# v0_6_0.net
KiCad netlist of a schematic drawn in EAGLE
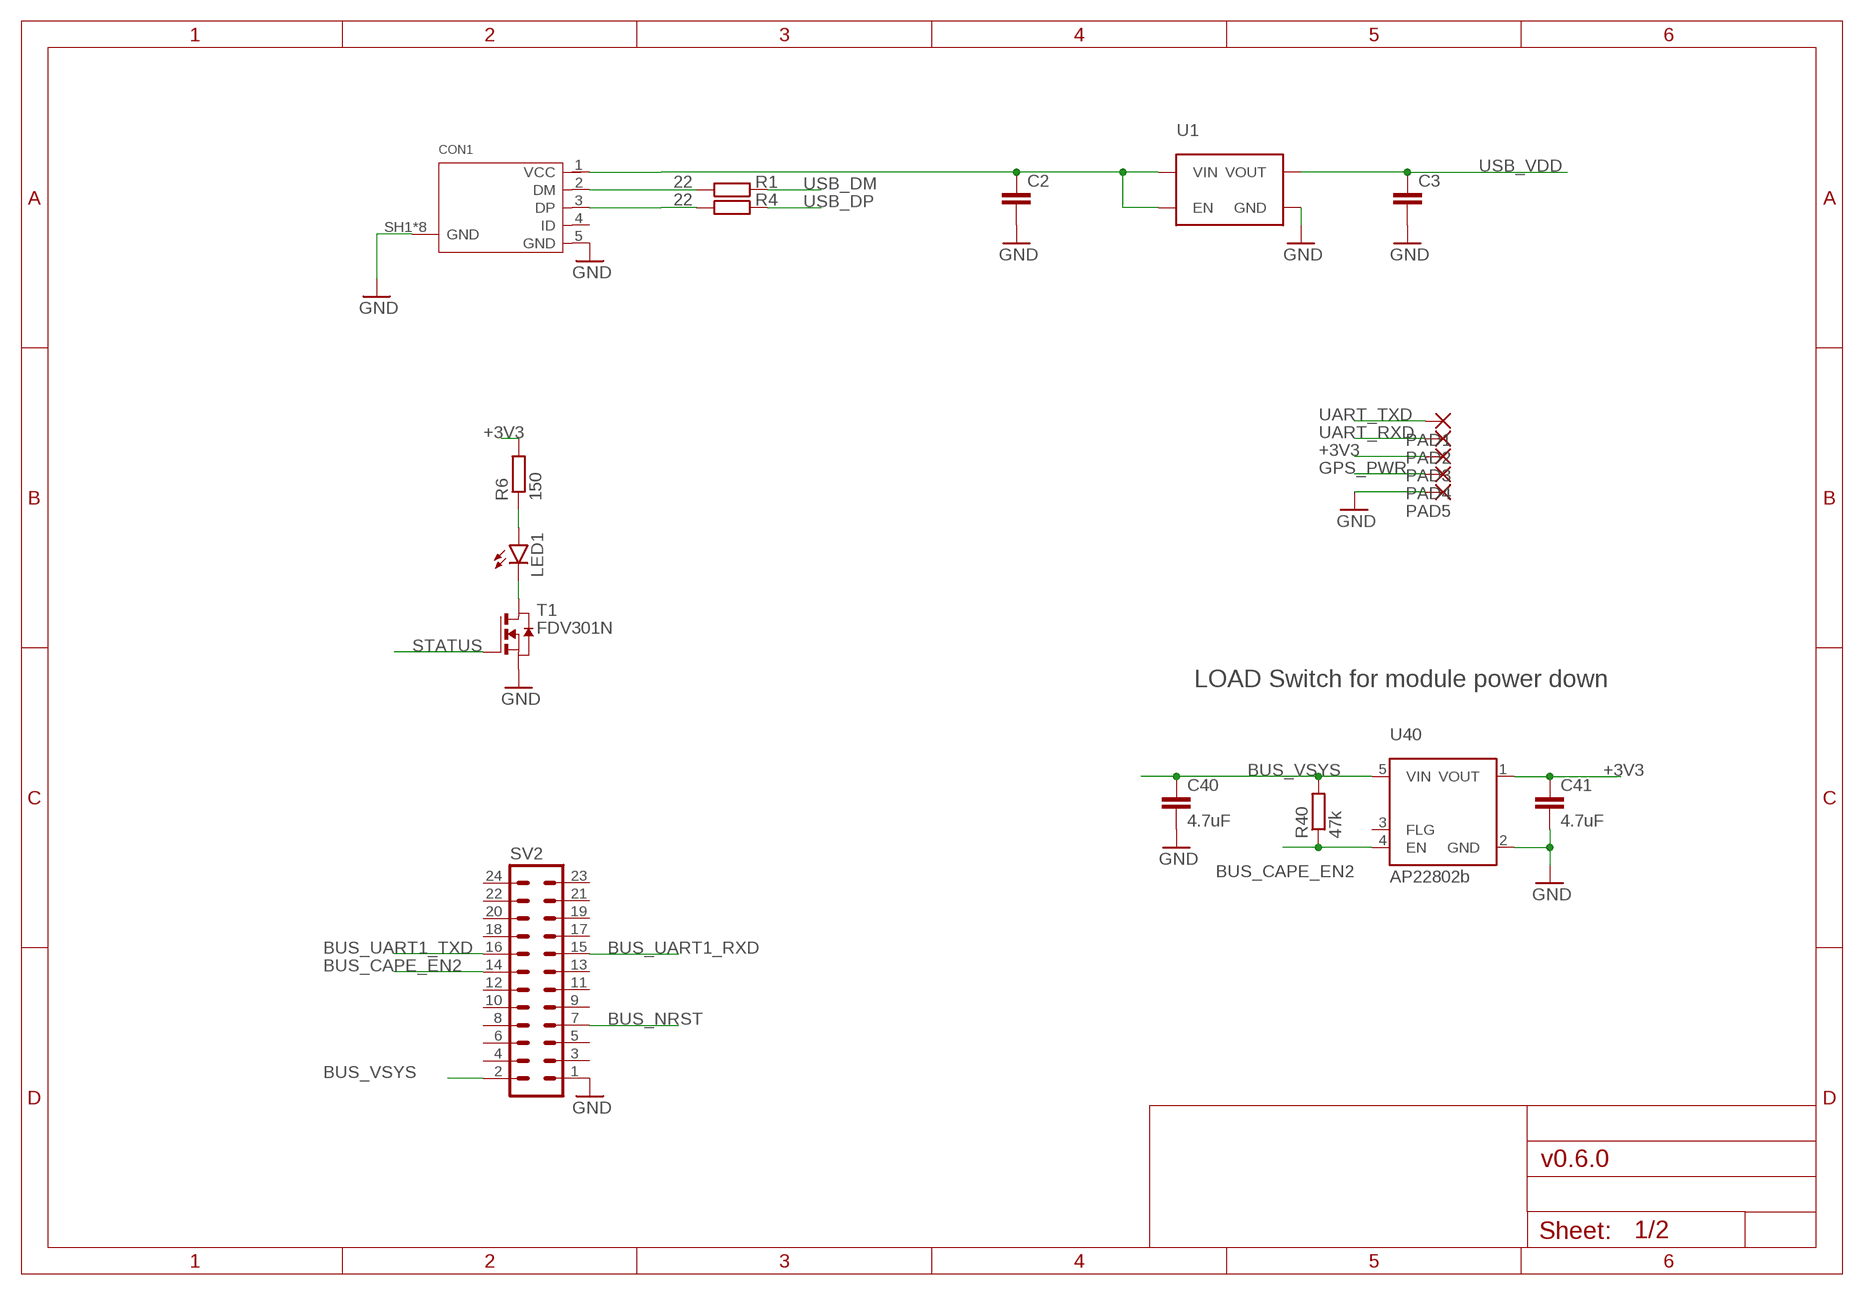
[diagram p0: schematic, sheet 1]
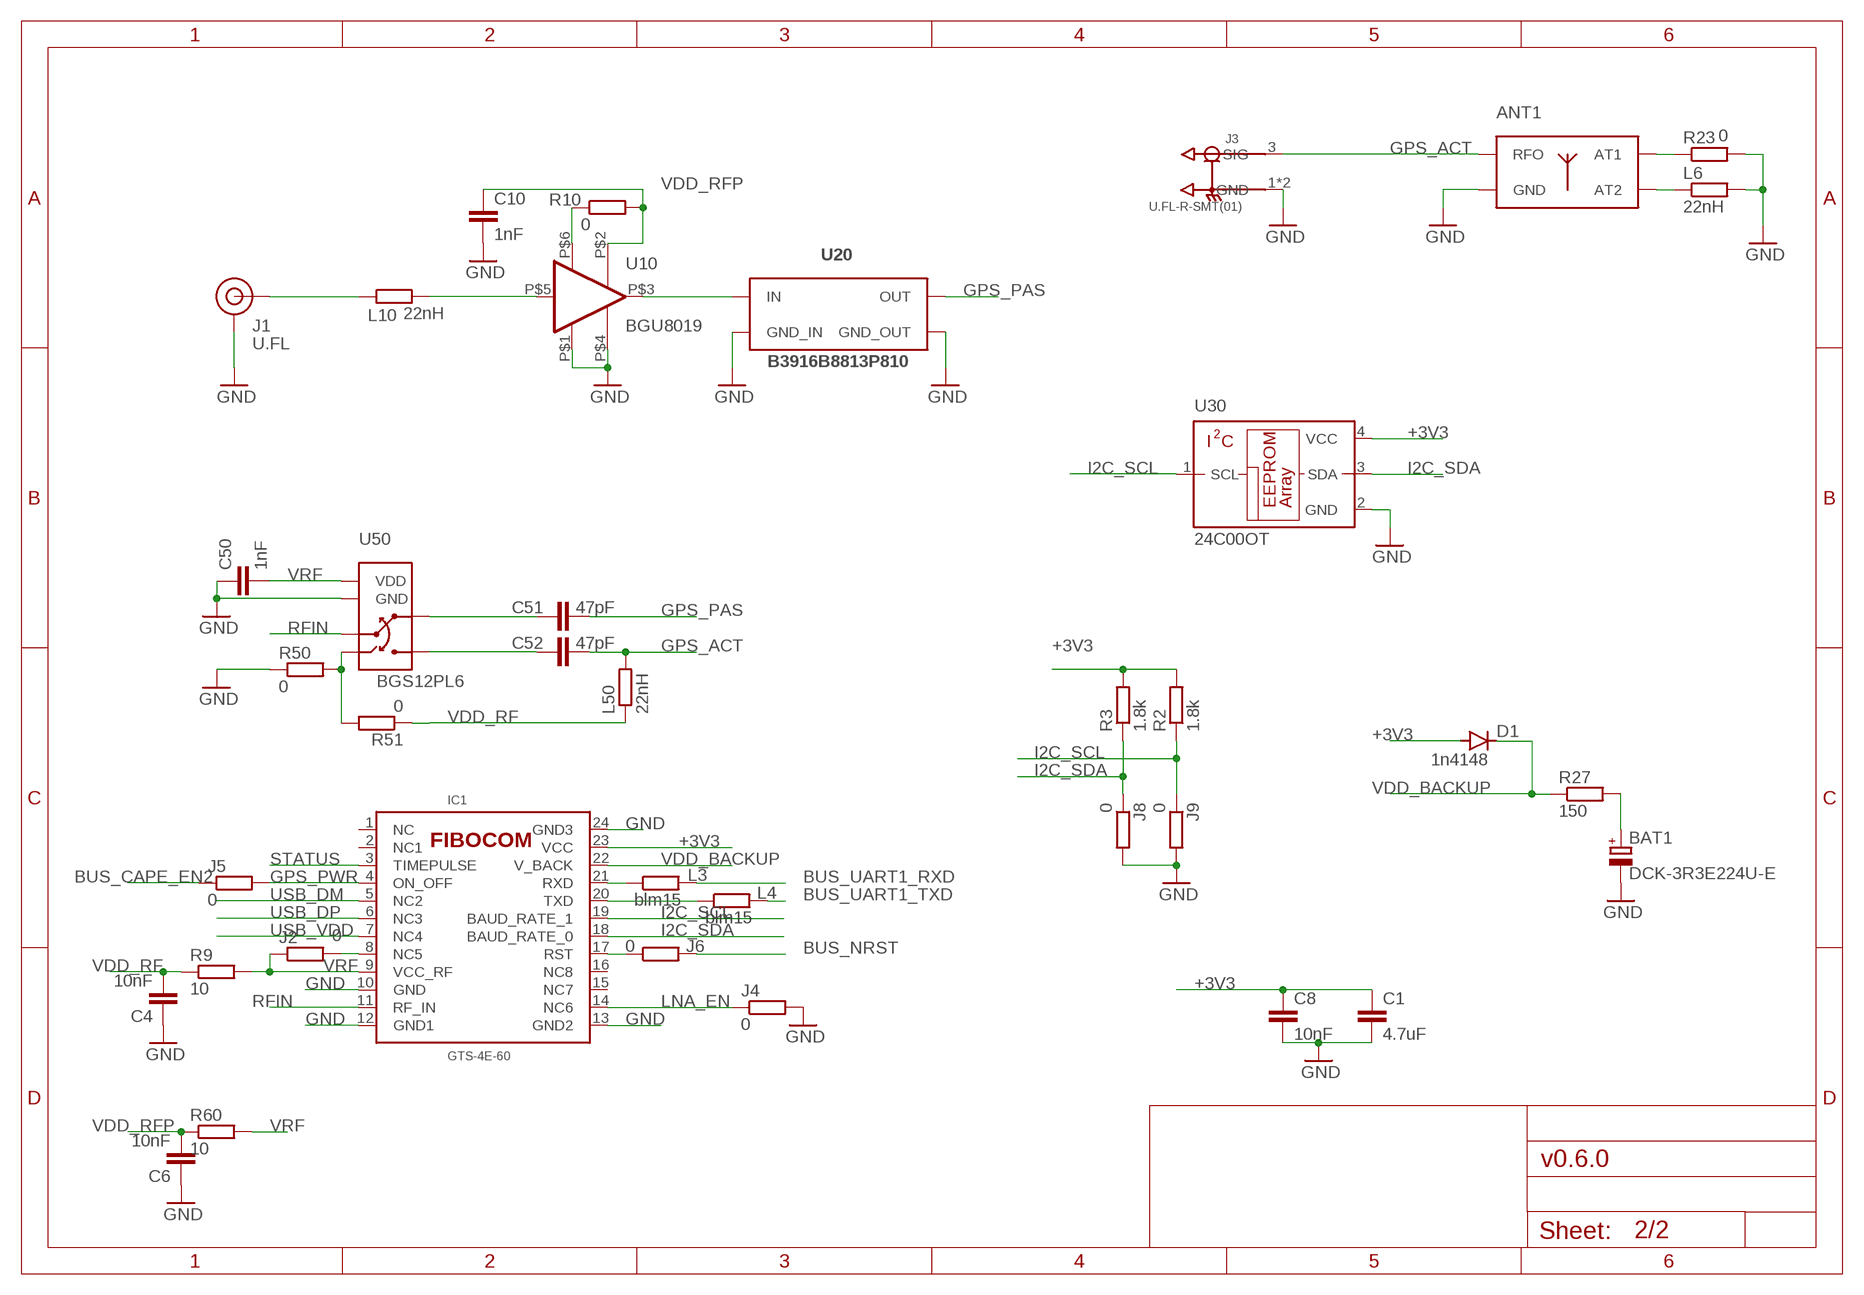
[diagram p1: schematic, sheet 2]

(export (version "E")
  (design (tool "Eeschema 10.0.6"))
  (components
    (comp (ref "ANT1")
      (value "M20047")
      (footprint "eagle-import:PCBCOMPONENT_1")
      (libsource (lib "eagle-import") (part "M20047"))
    )
    (comp (ref "BAT1")
      (value "DCK-3R3E224U-E")
      (footprint "eagle-import:621")
      (libsource (lib "eagle-import") (part "DCK-3R3E224U-E"))
    )
    (comp (ref "C1")
      (value "4.7uF")
      (footprint "eagle-import:C0603")
      (libsource (lib "eagle-import") (part "C-EUC0603"))
    )
    (comp (ref "C4")
      (value "10nF")
      (footprint "eagle-import:C0402")
      (libsource (lib "eagle-import") (part "C-EUC0402"))
    )
    (comp (ref "C6")
      (value "10nF")
      (footprint "eagle-import:C0402")
      (libsource (lib "eagle-import") (part "C-EUC0402"))
    )
    (comp (ref "C8")
      (value "10nF")
      (footprint "eagle-import:C0402")
      (libsource (lib "eagle-import") (part "C-EUC0402"))
    )
    (comp (ref "C10")
      (value "1nF")
      (footprint "eagle-import:C0402")
      (libsource (lib "eagle-import") (part "C-EUC0402"))
    )
    (comp (ref "C50")
      (value "1nF")
      (footprint "eagle-import:C0402")
      (libsource (lib "eagle-import") (part "C-EUC0402"))
    )
    (comp (ref "C51")
      (value "47pF")
      (footprint "eagle-import:C0402")
      (libsource (lib "eagle-import") (part "C-EUC0402"))
    )
    (comp (ref "C52")
      (value "47pF")
      (footprint "eagle-import:C0402")
      (libsource (lib "eagle-import") (part "C-EUC0402"))
    )
    (comp (ref "D1")
      (value "1n4148")
      (footprint "eagle-import:SOD323-R")
      (libsource (lib "eagle-import") (part "DIODE-SOD323-R"))
    )
    (comp (ref "IC1")
      (value "GTS-4E-60")
      (footprint "eagle-import:_GTS_4E_60")
      (libsource (lib "eagle-import") (part "GTS-4E-60"))
    )
    (comp (ref "J1")
      (value "U.FL")
      (footprint "eagle-import:U.FL")
      (libsource (lib "eagle-import") (part "U.FL2PIN"))
    )
    (comp (ref "J2")
      (value "0")
      (footprint "eagle-import:R0402")
      (libsource (lib "eagle-import") (part "R-EU_R0402"))
    )
    (comp (ref "J3")
      (value "U.FL-R-SMT(01)")
      (footprint "eagle-import:HRS_U.FL-R-SMT(01)")
      (fields (field (name "MF") "Hirose") (field (name "MP") "U.FL-R-SMT_01_"))
      (libsource (lib "eagle-import") (part "U.FL-R-SMT(01)"))
    )
    (comp (ref "J4")
      (value "0")
      (footprint "eagle-import:R0402")
      (libsource (lib "eagle-import") (part "R-EU_R0402"))
    )
    (comp (ref "J5")
      (value "0")
      (footprint "eagle-import:R0402")
      (libsource (lib "eagle-import") (part "R-EU_R0402"))
    )
    (comp (ref "J6")
      (value "0")
      (footprint "eagle-import:R0402")
      (libsource (lib "eagle-import") (part "R-EU_R0402"))
    )
    (comp (ref "J8")
      (value "0")
      (footprint "eagle-import:R0402")
      (libsource (lib "eagle-import") (part "R-EU_R0402"))
    )
    (comp (ref "J9")
      (value "0")
      (footprint "eagle-import:R0402")
      (libsource (lib "eagle-import") (part "R-EU_R0402"))
    )
    (comp (ref "L3")
      (value "blm15")
      (footprint "eagle-import:R0402")
      (libsource (lib "eagle-import") (part "R-EU_R0402"))
    )
    (comp (ref "L4")
      (value "blm15")
      (footprint "eagle-import:R0402")
      (libsource (lib "eagle-import") (part "R-EU_R0402"))
    )
    (comp (ref "L6")
      (value "22nH")
      (footprint "eagle-import:R0402")
      (libsource (lib "eagle-import") (part "R-EU_R0402"))
    )
    (comp (ref "L10")
      (value "22nH")
      (footprint "eagle-import:R0402")
      (libsource (lib "eagle-import") (part "R-EU_R0402"))
    )
    (comp (ref "L50")
      (value "22nH")
      (footprint "eagle-import:R0402")
      (libsource (lib "eagle-import") (part "R-EU_R0402"))
    )
    (comp (ref "R2")
      (value "1.8k")
      (footprint "eagle-import:R0402")
      (libsource (lib "eagle-import") (part "R-EU_R0402"))
    )
    (comp (ref "R3")
      (value "1.8k")
      (footprint "eagle-import:R0402")
      (libsource (lib "eagle-import") (part "R-EU_R0402"))
    )
    (comp (ref "R9")
      (value "10")
      (footprint "eagle-import:R0402")
      (libsource (lib "eagle-import") (part "R-EU_R0402"))
    )
    (comp (ref "R10")
      (value "0")
      (footprint "eagle-import:R0402")
      (libsource (lib "eagle-import") (part "R-EU_R0402"))
    )
    (comp (ref "R23")
      (value "0")
      (footprint "eagle-import:R0402")
      (libsource (lib "eagle-import") (part "R-EU_R0402"))
    )
    (comp (ref "R27")
      (value "150")
      (footprint "eagle-import:R0402")
      (libsource (lib "eagle-import") (part "R-EU_R0402"))
    )
    (comp (ref "R50")
      (value "0")
      (footprint "eagle-import:R0402")
      (libsource (lib "eagle-import") (part "R-EU_R0402"))
    )
    (comp (ref "R51")
      (value "0")
      (footprint "eagle-import:R0402")
      (libsource (lib "eagle-import") (part "R-EU_R0402"))
    )
    (comp (ref "R60")
      (value "10")
      (footprint "eagle-import:R0402")
      (libsource (lib "eagle-import") (part "R-EU_R0402"))
    )
    (comp (ref "U10")
      (value "BGU8019")
      (footprint "eagle-import:XSON6")
      (libsource (lib "eagle-import") (part "BGU8019"))
    )
    (comp (ref "U20")
      (value "B3916B8813P810")
      (footprint "eagle-import:XSON5")
      (libsource (lib "eagle-import") (part "B3916B8813P810"))
    )
    (comp (ref "U30")
      (value "24C00OT")
      (footprint "eagle-import:SOT23-5L")
      (fields (field (name "MF") "MICROCHIP") (field (name "MPN") "24C00T-I/OT"))
      (libsource (lib "eagle-import") (part "2400OTC"))
    )
    (comp (ref "U50")
      (value "BGS12PL6")
      (footprint "eagle-import:TSLP-6-4")
      (libsource (lib "eagle-import") (part "BGS12PL6"))
    )
    (comp (ref "C2")
      (value "C-EUC0603")
      (footprint "eagle-import:C0603")
      (libsource (lib "eagle-import") (part "C-EUC0603"))
    )
    (comp (ref "C3")
      (value "C-EUC0603")
      (footprint "eagle-import:C0603")
      (libsource (lib "eagle-import") (part "C-EUC0603"))
    )
    (comp (ref "C40")
      (value "4.7uF")
      (footprint "eagle-import:C0603")
      (libsource (lib "eagle-import") (part "C-EUC0603"))
    )
    (comp (ref "C41")
      (value "4.7uF")
      (footprint "eagle-import:C0603")
      (libsource (lib "eagle-import") (part "C-EUC0603"))
    )
    (comp (ref "CON1")
      (value "10118194-0001LF")
      (footprint "eagle-import:10118194")
      (libsource (lib "eagle-import") (part "10118194-0001LF"))
    )
    (comp (ref "LED1")
      (value "LEDCHIP-LED0603")
      (footprint "eagle-import:CHIP-LED0603")
      (libsource (lib "eagle-import") (part "LEDCHIP-LED0603"))
    )
    (comp (ref "PAD1")
      (value "1,6/0,9")
      (footprint "eagle-import:1,6_0,9")
      (libsource (lib "eagle-import") (part "1,6/0,9"))
    )
    (comp (ref "PAD2")
      (value "1,6/0,9")
      (footprint "eagle-import:1,6_0,9")
      (libsource (lib "eagle-import") (part "1,6/0,9"))
    )
    (comp (ref "PAD3")
      (value "1,6/0,9")
      (footprint "eagle-import:1,6_0,9")
      (libsource (lib "eagle-import") (part "1,6/0,9"))
    )
    (comp (ref "PAD4")
      (value "1,6/0,9")
      (footprint "eagle-import:1,6_0,9")
      (libsource (lib "eagle-import") (part "1,6/0,9"))
    )
    (comp (ref "PAD5")
      (value "1,6/0,9")
      (footprint "eagle-import:1,6_0,9")
      (libsource (lib "eagle-import") (part "1,6/0,9"))
    )
    (comp (ref "R1")
      (value "22")
      (footprint "eagle-import:R0402")
      (libsource (lib "eagle-import") (part "R-EU_R0402"))
    )
    (comp (ref "R4")
      (value "22")
      (footprint "eagle-import:R0402")
      (libsource (lib "eagle-import") (part "R-EU_R0402"))
    )
    (comp (ref "R6")
      (value "150")
      (footprint "eagle-import:R0402")
      (libsource (lib "eagle-import") (part "R-EU_R0402"))
    )
    (comp (ref "R40")
      (value "47k")
      (footprint "eagle-import:R0402")
      (libsource (lib "eagle-import") (part "R-EU_R0402"))
    )
    (comp (ref "SV2")
      (value "MA12-2")
      (footprint "eagle-import:MA12-2")
      (libsource (lib "eagle-import") (part "MA12-2"))
    )
    (comp (ref "T1")
      (value "FDV301N")
      (footprint "eagle-import:SOT-23")
      (libsource (lib "eagle-import") (part "NMOSSOT23"))
    )
    (comp (ref "U1")
      (value "MIC94310")
      (footprint "eagle-import:SOT95P280X110-5")
      (libsource (lib "eagle-import") (part "MIC94310"))
    )
    (comp (ref "U40")
      (value "AP22802b")
      (footprint "eagle-import:SOT25")
      (libsource (lib "eagle-import") (part "AP22802"))
    )
  )
  (nets
    (net (code "1") (name "+3V3") (class "Default")
      (node (ref "C1") (pin "1") (pinfunction "1_1") (pintype "passive"))
      (node (ref "C41") (pin "1") (pinfunction "1_1") (pintype "passive"))
      (node (ref "C8") (pin "1") (pinfunction "1_1") (pintype "passive"))
      (node (ref "D1") (pin "A") (pinfunction "A_A") (pintype "passive"))
      (node (ref "IC1") (pin "23") (pinfunction "VCC_23") (pintype "bidirectional"))
      (node (ref "PAD3") (pin "1") (pinfunction "P_1") (pintype "passive"))
      (node (ref "R2") (pin "2") (pinfunction "2_2") (pintype "passive"))
      (node (ref "R3") (pin "2") (pinfunction "2_2") (pintype "passive"))
      (node (ref "R6") (pin "2") (pinfunction "2_2") (pintype "passive"))
      (node (ref "U30") (pin "4") (pinfunction "VCC_4") (pintype "power_in"))
      (node (ref "U40") (pin "1") (pinfunction "VOUT_1") (pintype "bidirectional"))
    )
    (net (code "2") (name "BUS_CAPE_EN2") (class "Default")
      (node (ref "J5") (pin "1") (pinfunction "1_1") (pintype "passive"))
      (node (ref "R40") (pin "1") (pinfunction "1_1") (pintype "passive"))
      (node (ref "SV2") (pin "14") (pinfunction "14_14") (pintype "passive"))
      (node (ref "U40") (pin "4") (pinfunction "EN_4") (pintype "bidirectional"))
    )
    (net (code "3") (name "BUS_NRST") (class "Default")
      (node (ref "J6") (pin "2") (pinfunction "2_2") (pintype "passive"))
      (node (ref "SV2") (pin "7") (pinfunction "7_7") (pintype "passive"))
    )
    (net (code "4") (name "BUS_UART1_RXD") (class "Default")
      (node (ref "L3") (pin "2") (pinfunction "2_2") (pintype "passive"))
      (node (ref "SV2") (pin "15") (pinfunction "15_15") (pintype "passive"))
    )
    (net (code "5") (name "BUS_UART1_TXD") (class "Default")
      (node (ref "L4") (pin "2") (pinfunction "2_2") (pintype "passive"))
      (node (ref "SV2") (pin "16") (pinfunction "16_16") (pintype "passive"))
    )
    (net (code "6") (name "BUS_VSYS") (class "Default")
      (node (ref "C40") (pin "1") (pinfunction "1_1") (pintype "passive"))
      (node (ref "R40") (pin "2") (pinfunction "2_2") (pintype "passive"))
      (node (ref "SV2") (pin "2") (pinfunction "2_2") (pintype "passive"))
      (node (ref "U40") (pin "5") (pinfunction "VIN_5") (pintype "bidirectional"))
    )
    (net (code "7") (name "GND") (class "Default")
      (node (ref "ANT1") (pin "2") (pinfunction "GND_2") (pintype "power_in"))
      (node (ref "ANT1") (pin "3") (pinfunction "GND_3") (pintype "power_in"))
      (node (ref "ANT1") (pin "4") (pinfunction "GND_4") (pintype "power_in"))
      (node (ref "BAT1") (pin "-") (pinfunction "-_-") (pintype "passive"))
      (node (ref "C1") (pin "2") (pinfunction "2_2") (pintype "passive"))
      (node (ref "C10") (pin "2") (pinfunction "2_2") (pintype "passive"))
      (node (ref "C2") (pin "2") (pinfunction "2_2") (pintype "passive"))
      (node (ref "C3") (pin "2") (pinfunction "2_2") (pintype "passive"))
      (node (ref "C4") (pin "1") (pinfunction "1_1") (pintype "passive"))
      (node (ref "C40") (pin "2") (pinfunction "2_2") (pintype "passive"))
      (node (ref "C41") (pin "2") (pinfunction "2_2") (pintype "passive"))
      (node (ref "C50") (pin "1") (pinfunction "1_1") (pintype "passive"))
      (node (ref "C6") (pin "1") (pinfunction "1_1") (pintype "passive"))
      (node (ref "C8") (pin "2") (pinfunction "2_2") (pintype "passive"))
      (node (ref "CON1") (pin "5") (pinfunction "GND_5") (pintype "bidirectional"))
      (node (ref "CON1") (pin "SH1") (pinfunction "GND_SH1") (pintype "bidirectional"))
      (node (ref "CON1") (pin "SH2") (pinfunction "GND_SH2") (pintype "bidirectional"))
      (node (ref "CON1") (pin "SH3") (pinfunction "GND_SH3") (pintype "bidirectional"))
      (node (ref "CON1") (pin "SH4") (pinfunction "GND_SH4") (pintype "bidirectional"))
      (node (ref "CON1") (pin "SH5") (pinfunction "GND_SH5") (pintype "bidirectional"))
      (node (ref "CON1") (pin "SH6") (pinfunction "GND_SH6") (pintype "bidirectional"))
      (node (ref "CON1") (pin "SH7") (pinfunction "GND_SH7") (pintype "bidirectional"))
      (node (ref "CON1") (pin "SH8") (pinfunction "GND_SH8") (pintype "bidirectional"))
      (node (ref "IC1") (pin "10") (pinfunction "GND_10") (pintype "bidirectional"))
      (node (ref "IC1") (pin "12") (pinfunction "GND1_12") (pintype "bidirectional"))
      (node (ref "IC1") (pin "13") (pinfunction "GND2_13") (pintype "bidirectional"))
      (node (ref "IC1") (pin "24") (pinfunction "GND3_24") (pintype "bidirectional"))
      (node (ref "J1") (pin "1") (pinfunction "GND_1") (pintype "bidirectional"))
      (node (ref "J1") (pin "2") (pinfunction "GND_2") (pintype "bidirectional"))
      (node (ref "J3") (pin "1") (pinfunction "GND_1") (pintype "passive"))
      (node (ref "J3") (pin "2") (pinfunction "GND_2") (pintype "passive"))
      (node (ref "J4") (pin "2") (pinfunction "2_2") (pintype "passive"))
      (node (ref "J8") (pin "2") (pinfunction "2_2") (pintype "passive"))
      (node (ref "J9") (pin "2") (pinfunction "2_2") (pintype "passive"))
      (node (ref "L6") (pin "2") (pinfunction "2_2") (pintype "passive"))
      (node (ref "PAD5") (pin "1") (pinfunction "P_1") (pintype "passive"))
      (node (ref "R23") (pin "2") (pinfunction "2_2") (pintype "passive"))
      (node (ref "R50") (pin "1") (pinfunction "1_1") (pintype "passive"))
      (node (ref "SV2") (pin "1") (pinfunction "1_1") (pintype "passive"))
      (node (ref "T1") (pin "2") (pinfunction "S_2") (pintype "passive"))
      (node (ref "U1") (pin "2") (pinfunction "GND_2") (pintype "bidirectional"))
      (node (ref "U10") (pin "P$1") (pinfunction "GND_P$1") (pintype "power_in"))
      (node (ref "U10") (pin "P$4") (pinfunction "GND_RF_P$4") (pintype "passive"))
      (node (ref "U20") (pin "2") (pinfunction "GND_IN_2") (pintype "bidirectional"))
      (node (ref "U20") (pin "3") (pinfunction "GND_OUT_3") (pintype "bidirectional"))
      (node (ref "U20") (pin "5") (pinfunction "GND_IN_5") (pintype "bidirectional"))
      (node (ref "U30") (pin "2") (pinfunction "GND_2") (pintype "power_in"))
      (node (ref "U40") (pin "2") (pinfunction "GND_2") (pintype "bidirectional"))
      (node (ref "U50") (pin "P$2") (pinfunction "GND_P$2") (pintype "power_in"))
    )
    (net (code "8") (name "GPS_ACT") (class "Default")
      (node (ref "ANT1") (pin "5") (pinfunction "RFO_5") (pintype "input"))
      (node (ref "C52") (pin "2") (pinfunction "2_2") (pintype "passive"))
      (node (ref "J3") (pin "3") (pinfunction "SIG_3") (pintype "passive"))
      (node (ref "L50") (pin "2") (pinfunction "2_2") (pintype "passive"))
    )
    (net (code "9") (name "GPS_PAS") (class "Default")
      (node (ref "C51") (pin "2") (pinfunction "2_2") (pintype "passive"))
      (node (ref "U20") (pin "4") (pinfunction "OUT_4") (pintype "bidirectional"))
    )
    (net (code "10") (name "GPS_PWR") (class "Default")
      (node (ref "IC1") (pin "4") (pinfunction "ON_OFF_4") (pintype "bidirectional"))
      (node (ref "J5") (pin "2") (pinfunction "2_2") (pintype "passive"))
      (node (ref "PAD4") (pin "1") (pinfunction "P_1") (pintype "passive"))
    )
    (net (code "11") (name "I2C_SCL") (class "Default")
      (node (ref "IC1") (pin "19") (pinfunction "BAUD_RATE_1_19") (pintype "bidirectional"))
      (node (ref "J9") (pin "1") (pinfunction "1_1") (pintype "passive"))
      (node (ref "R2") (pin "1") (pinfunction "1_1") (pintype "passive"))
      (node (ref "U30") (pin "1") (pinfunction "SCL_1") (pintype "input"))
    )
    (net (code "12") (name "I2C_SDA") (class "Default")
      (node (ref "IC1") (pin "18") (pinfunction "BAUD_RATE_0_18") (pintype "bidirectional"))
      (node (ref "J8") (pin "1") (pinfunction "1_1") (pintype "passive"))
      (node (ref "R3") (pin "1") (pinfunction "1_1") (pintype "passive"))
      (node (ref "U30") (pin "3") (pinfunction "SDA_3") (pintype "bidirectional"))
    )
    (net (code "13") (name "LNA_EN") (class "Default")
      (node (ref "IC1") (pin "14") (pinfunction "NC6_14") (pintype "bidirectional"))
      (node (ref "J4") (pin "1") (pinfunction "1_1") (pintype "passive"))
    )
    (net (code "14") (name "Net-(ANT1-AT1)") (class "Default")
      (node (ref "ANT1") (pin "1") (pinfunction "AT1_1") (pintype "bidirectional"))
      (node (ref "R23") (pin "1") (pinfunction "1_1") (pintype "passive"))
    )
    (net (code "15") (name "Net-(ANT1-AT2)") (class "Default")
      (node (ref "ANT1") (pin "6") (pinfunction "AT2_6") (pintype "bidirectional"))
      (node (ref "L6") (pin "1") (pinfunction "1_1") (pintype "passive"))
    )
    (net (code "16") (name "Net-(BAT1-Pad+)") (class "Default")
      (node (ref "BAT1") (pin "+") (pinfunction "+_+") (pintype "passive"))
      (node (ref "R27") (pin "2") (pinfunction "2_2") (pintype "passive"))
    )
    (net (code "17") (name "Net-(CON1-DM)") (class "Default")
      (node (ref "CON1") (pin "2") (pinfunction "DM_2") (pintype "bidirectional"))
      (node (ref "R1") (pin "2") (pinfunction "2_2") (pintype "passive"))
    )
    (net (code "18") (name "Net-(CON1-DP)") (class "Default")
      (node (ref "CON1") (pin "3") (pinfunction "DP_3") (pintype "bidirectional"))
      (node (ref "R4") (pin "2") (pinfunction "2_2") (pintype "passive"))
    )
    (net (code "19") (name "Net-(CON1-VCC)") (class "Default")
      (node (ref "C2") (pin "1") (pinfunction "1_1") (pintype "passive"))
      (node (ref "CON1") (pin "1") (pinfunction "VCC_1") (pintype "bidirectional"))
      (node (ref "U1") (pin "1") (pinfunction "VIN_1") (pintype "bidirectional"))
      (node (ref "U1") (pin "3") (pinfunction "EN_3") (pintype "bidirectional"))
    )
    (net (code "20") (name "Net-(IC1-NC5)") (class "Default")
      (node (ref "IC1") (pin "8") (pinfunction "NC5_8") (pintype "bidirectional"))
      (node (ref "J2") (pin "2") (pinfunction "2_2") (pintype "passive"))
    )
    (net (code "21") (name "Net-(IC1-RST)") (class "Default")
      (node (ref "IC1") (pin "17") (pinfunction "RST_17") (pintype "bidirectional"))
      (node (ref "J6") (pin "1") (pinfunction "1_1") (pintype "passive"))
    )
    (net (code "22") (name "Net-(J1-SIGNAL)") (class "Default")
      (node (ref "J1") (pin "FEED") (pinfunction "SIGNAL_FEED") (pintype "bidirectional"))
      (node (ref "L10") (pin "1") (pinfunction "1_1") (pintype "passive"))
    )
    (net (code "23") (name "Net-(LED1-PadA)") (class "Default")
      (node (ref "LED1") (pin "A") (pinfunction "A_A") (pintype "passive"))
      (node (ref "R6") (pin "1") (pinfunction "1_1") (pintype "passive"))
    )
    (net (code "24") (name "Net-(T1-D)") (class "Default")
      (node (ref "LED1") (pin "C") (pinfunction "C_C") (pintype "passive"))
      (node (ref "T1") (pin "1") (pinfunction "D_1") (pintype "passive"))
    )
    (net (code "25") (name "Net-(U10-ENABLE)") (class "Default")
      (node (ref "R10") (pin "1") (pinfunction "1_1") (pintype "passive"))
      (node (ref "U10") (pin "P$6") (pinfunction "ENABLE_P$6") (pintype "power_in"))
    )
    (net (code "26") (name "Net-(U10-RF_IN)") (class "Default")
      (node (ref "L10") (pin "2") (pinfunction "2_2") (pintype "passive"))
      (node (ref "U10") (pin "P$5") (pinfunction "RF_IN_P$5") (pintype "input"))
    )
    (net (code "27") (name "Net-(U10-RF_OUT)") (class "Default")
      (node (ref "U10") (pin "P$3") (pinfunction "RF_OUT_P$3") (pintype "output"))
      (node (ref "U20") (pin "1") (pinfunction "IN_1") (pintype "bidirectional"))
    )
    (net (code "28") (name "Net-(U50-P$4)") (class "Default")
      (node (ref "R50") (pin "2") (pinfunction "2_2") (pintype "passive"))
      (node (ref "R51") (pin "2") (pinfunction "2_2") (pintype "passive"))
      (node (ref "U50") (pin "P$6") (pinfunction "P$4_P$6") (pintype "bidirectional"))
    )
    (net (code "29") (name "Net-(U50-RF1)") (class "Default")
      (node (ref "C51") (pin "1") (pinfunction "1_1") (pintype "passive"))
      (node (ref "U50") (pin "P$3") (pinfunction "RF1_P$3") (pintype "bidirectional"))
    )
    (net (code "30") (name "Net-(U50-RF2)") (class "Default")
      (node (ref "C52") (pin "1") (pinfunction "1_1") (pintype "passive"))
      (node (ref "U50") (pin "P$1") (pinfunction "RF2_P$1") (pintype "bidirectional"))
    )
    (net (code "31") (name "RFIN") (class "Default")
      (node (ref "IC1") (pin "11") (pinfunction "RF_IN_11") (pintype "bidirectional"))
      (node (ref "U50") (pin "P$5") (pinfunction "RFIN_P$5") (pintype "bidirectional"))
    )
    (net (code "32") (name "STATUS") (class "Default")
      (node (ref "IC1") (pin "3") (pinfunction "TIMEPULSE_3") (pintype "bidirectional"))
      (node (ref "T1") (pin "3") (pinfunction "G_3") (pintype "passive"))
    )
    (net (code "33") (name "UART_RXD") (class "Default")
      (node (ref "IC1") (pin "20") (pinfunction "TXD_20") (pintype "bidirectional"))
      (node (ref "L4") (pin "1") (pinfunction "1_1") (pintype "passive"))
      (node (ref "PAD2") (pin "1") (pinfunction "P_1") (pintype "passive"))
    )
    (net (code "34") (name "UART_TXD") (class "Default")
      (node (ref "IC1") (pin "21") (pinfunction "RXD_21") (pintype "bidirectional"))
      (node (ref "L3") (pin "1") (pinfunction "1_1") (pintype "passive"))
      (node (ref "PAD1") (pin "1") (pinfunction "P_1") (pintype "passive"))
    )
    (net (code "35") (name "USB_DM") (class "Default")
      (node (ref "IC1") (pin "5") (pinfunction "NC2_5") (pintype "bidirectional"))
      (node (ref "R1") (pin "1") (pinfunction "1_1") (pintype "passive"))
    )
    (net (code "36") (name "USB_DP") (class "Default")
      (node (ref "IC1") (pin "6") (pinfunction "NC3_6") (pintype "bidirectional"))
      (node (ref "R4") (pin "1") (pinfunction "1_1") (pintype "passive"))
    )
    (net (code "37") (name "USB_VDD") (class "Default")
      (node (ref "C3") (pin "1") (pinfunction "1_1") (pintype "passive"))
      (node (ref "IC1") (pin "7") (pinfunction "NC4_7") (pintype "bidirectional"))
      (node (ref "U1") (pin "5") (pinfunction "VOUT_5") (pintype "bidirectional"))
    )
    (net (code "38") (name "VDD_BACKUP") (class "Default")
      (node (ref "D1") (pin "C") (pinfunction "C_C") (pintype "passive"))
      (node (ref "IC1") (pin "22") (pinfunction "V_BACK_22") (pintype "bidirectional"))
      (node (ref "R27") (pin "1") (pinfunction "1_1") (pintype "passive"))
    )
    (net (code "39") (name "VDD_RF") (class "Default")
      (node (ref "C4") (pin "2") (pinfunction "2_2") (pintype "passive"))
      (node (ref "L50") (pin "1") (pinfunction "1_1") (pintype "passive"))
      (node (ref "R51") (pin "1") (pinfunction "1_1") (pintype "passive"))
      (node (ref "R9") (pin "1") (pinfunction "1_1") (pintype "passive"))
    )
    (net (code "40") (name "VDD_RFP") (class "Default")
      (node (ref "C10") (pin "1") (pinfunction "1_1") (pintype "passive"))
      (node (ref "C6") (pin "2") (pinfunction "2_2") (pintype "passive"))
      (node (ref "R10") (pin "2") (pinfunction "2_2") (pintype "passive"))
      (node (ref "R60") (pin "1") (pinfunction "1_1") (pintype "passive"))
      (node (ref "U10") (pin "P$2") (pinfunction "VCC_P$2") (pintype "passive"))
    )
    (net (code "41") (name "VRF") (class "Default")
      (node (ref "C50") (pin "2") (pinfunction "2_2") (pintype "passive"))
      (node (ref "IC1") (pin "9") (pinfunction "VCC_RF_9") (pintype "bidirectional"))
      (node (ref "J2") (pin "1") (pinfunction "1_1") (pintype "passive"))
      (node (ref "R60") (pin "2") (pinfunction "2_2") (pintype "passive"))
      (node (ref "R9") (pin "2") (pinfunction "2_2") (pintype "passive"))
      (node (ref "U50") (pin "P$4") (pinfunction "VDD_P$4") (pintype "power_in"))
    )
    (net (code "42") (name "unconnected-(CON1-ID-Pad4)") (class "Default")
      (node (ref "CON1") (pin "4") (pinfunction "ID_4") (pintype "bidirectional"))
    )
    (net (code "43") (name "unconnected-(IC1-NC-Pad1)") (class "Default")
      (node (ref "IC1") (pin "1") (pinfunction "NC_1") (pintype "bidirectional"))
    )
    (net (code "44") (name "unconnected-(IC1-NC1-Pad2)") (class "Default")
      (node (ref "IC1") (pin "2") (pinfunction "NC1_2") (pintype "bidirectional"))
    )
    (net (code "45") (name "unconnected-(IC1-NC7-Pad15)") (class "Default")
      (node (ref "IC1") (pin "15") (pinfunction "NC7_15") (pintype "bidirectional"))
    )
    (net (code "46") (name "unconnected-(IC1-NC8-Pad16)") (class "Default")
      (node (ref "IC1") (pin "16") (pinfunction "NC8_16") (pintype "bidirectional"))
    )
    (net (code "47") (name "unconnected-(SV2-Pad3)") (class "Default")
      (node (ref "SV2") (pin "3") (pinfunction "3_3") (pintype "passive"))
    )
    (net (code "48") (name "unconnected-(SV2-Pad4)") (class "Default")
      (node (ref "SV2") (pin "4") (pinfunction "4_4") (pintype "passive"))
    )
    (net (code "49") (name "unconnected-(SV2-Pad5)") (class "Default")
      (node (ref "SV2") (pin "5") (pinfunction "5_5") (pintype "passive"))
    )
    (net (code "50") (name "unconnected-(SV2-Pad6)") (class "Default")
      (node (ref "SV2") (pin "6") (pinfunction "6_6") (pintype "passive"))
    )
    (net (code "51") (name "unconnected-(SV2-Pad8)") (class "Default")
      (node (ref "SV2") (pin "8") (pinfunction "8_8") (pintype "passive"))
    )
    (net (code "52") (name "unconnected-(SV2-Pad9)") (class "Default")
      (node (ref "SV2") (pin "9") (pinfunction "9_9") (pintype "passive"))
    )
    (net (code "53") (name "unconnected-(SV2-Pad10)") (class "Default")
      (node (ref "SV2") (pin "10") (pinfunction "10_10") (pintype "passive"))
    )
    (net (code "54") (name "unconnected-(SV2-Pad11)") (class "Default")
      (node (ref "SV2") (pin "11") (pinfunction "11_11") (pintype "passive"))
    )
    (net (code "55") (name "unconnected-(SV2-Pad12)") (class "Default")
      (node (ref "SV2") (pin "12") (pinfunction "12_12") (pintype "passive"))
    )
    (net (code "56") (name "unconnected-(SV2-Pad13)") (class "Default")
      (node (ref "SV2") (pin "13") (pinfunction "13_13") (pintype "passive"))
    )
    (net (code "57") (name "unconnected-(SV2-Pad17)") (class "Default")
      (node (ref "SV2") (pin "17") (pinfunction "17_17") (pintype "passive"))
    )
    (net (code "58") (name "unconnected-(SV2-Pad18)") (class "Default")
      (node (ref "SV2") (pin "18") (pinfunction "18_18") (pintype "passive"))
    )
    (net (code "59") (name "unconnected-(SV2-Pad19)") (class "Default")
      (node (ref "SV2") (pin "19") (pinfunction "19_19") (pintype "passive"))
    )
    (net (code "60") (name "unconnected-(SV2-Pad20)") (class "Default")
      (node (ref "SV2") (pin "20") (pinfunction "20_20") (pintype "passive"))
    )
    (net (code "61") (name "unconnected-(SV2-Pad21)") (class "Default")
      (node (ref "SV2") (pin "21") (pinfunction "21_21") (pintype "passive"))
    )
    (net (code "62") (name "unconnected-(SV2-Pad22)") (class "Default")
      (node (ref "SV2") (pin "22") (pinfunction "22_22") (pintype "passive"))
    )
    (net (code "63") (name "unconnected-(SV2-Pad23)") (class "Default")
      (node (ref "SV2") (pin "23") (pinfunction "23_23") (pintype "passive"))
    )
    (net (code "64") (name "unconnected-(SV2-Pad24)") (class "Default")
      (node (ref "SV2") (pin "24") (pinfunction "24_24") (pintype "passive"))
    )
    (net (code "65") (name "unconnected-(U40-FLG-Pad3)") (class "Default")
      (node (ref "U40") (pin "3") (pinfunction "FLG_3") (pintype "bidirectional"))
    )
  )
)
